# Sheet1.net
KiCad netlist of a schematic drawn in Altium Designer
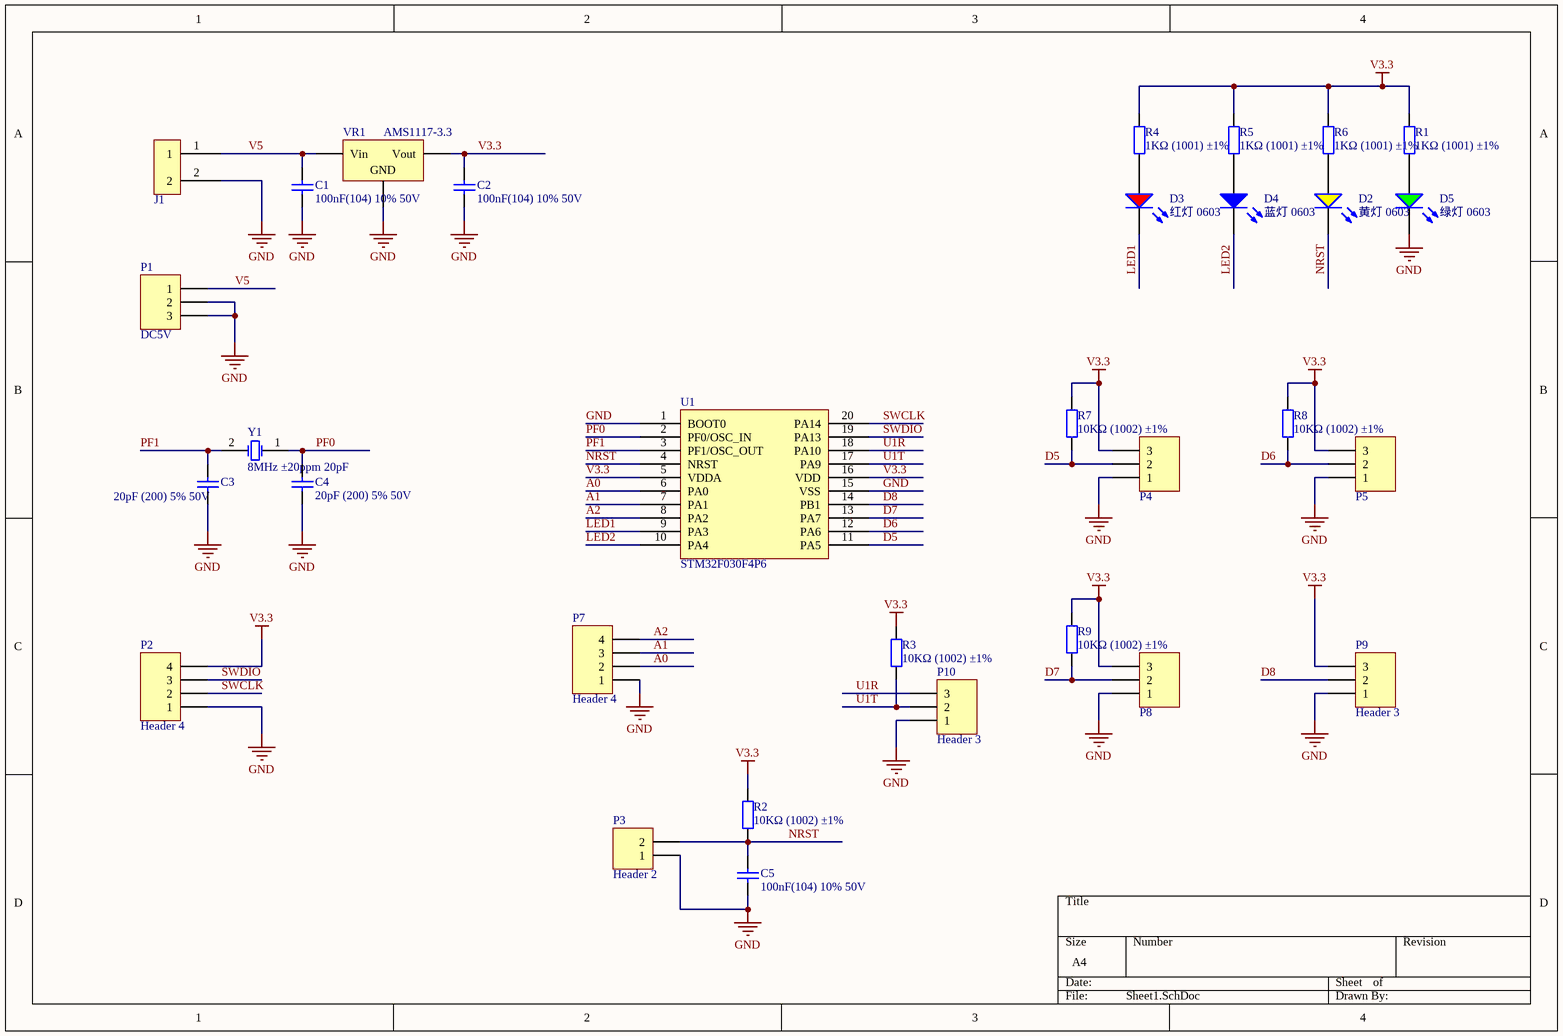
[diagram p0: Sheet1.SchDoc]

(export (version "E")
  (design (tool "Eeschema 10.0.6"))
  (components
    (comp (ref "C1")
      (value "100nF(104) 10% 50V")
      (footprint "0805_C")
      (description "贴片电容")
      (libsource (lib "Miscellaneous Devices LC") (part "0805 100nF(104) 10% 50V"))
    )
    (comp (ref "C2")
      (value "100nF(104) 10% 50V")
      (footprint "0805_C")
      (description "贴片电容")
      (libsource (lib "Miscellaneous Devices LC") (part "0805 100nF(104) 10% 50V"))
    )
    (comp (ref "C3")
      (value "20pF (200) 5% 50V")
      (footprint "0805_C")
      (description "贴片电容")
      (libsource (lib "Miscellaneous Devices LC") (part "0805 20pF (200) 5% 50V"))
    )
    (comp (ref "C4")
      (value "20pF (200) 5% 50V")
      (footprint "0805_C")
      (description "贴片电容")
      (libsource (lib "Miscellaneous Devices LC") (part "0805 20pF (200) 5% 50V"))
    )
    (comp (ref "C5")
      (value "100nF(104) 10% 50V")
      (footprint "0805_C")
      (description "贴片电容")
      (libsource (lib "Miscellaneous Devices LC") (part "0805 100nF(104) 10% 50V"))
    )
    (comp (ref "D2")
      (value "黄灯 0603")
      (footprint "0603_LED_S1")
      (description "发光二极管")
      (libsource (lib "Miscellaneous Devices LC") (part "0603 黄灯"))
    )
    (comp (ref "D3")
      (value "红灯 0603")
      (footprint "0603_LED_S1")
      (description "发光二极管")
      (libsource (lib "Miscellaneous Devices LC") (part "0603 红灯"))
    )
    (comp (ref "D4")
      (value "蓝灯 0603")
      (footprint "0603_LED_S1")
      (description "发光二极管")
      (libsource (lib "Miscellaneous Devices LC") (part "0603 蓝灯"))
    )
    (comp (ref "D5")
      (value "绿灯 0603")
      (footprint "0603_LED_S1")
      (description "发光二极管")
      (libsource (lib "Miscellaneous Devices LC") (part "0603 绿灯"))
    )
    (comp (ref "J1") (value "XK7.62-2P") (footprint "XK7.62-2P") (libsource (lib "CHK-I") (part "XK7.62-2P")))
    (comp (ref "P1")
      (value "DC5V")
      (footprint "DC005")
      (description "Header, 3-Pin")
      (fields (field (name "PUBLISHER") "Altium Limited"))
      (libsource (lib "") (part "Header 3_1"))
    )
    (comp (ref "P2")
      (value "Header 4")
      (footprint "HDR1X4")
      (description "Header, 4-Pin")
      (fields (field (name "PUBLISHER") "Altium Limited"))
      (libsource (lib "Miscellaneous Connectors") (part "Header 4"))
    )
    (comp (ref "P3")
      (value "Header 2")
      (footprint "HDR1X2")
      (description "Header, 2-Pin")
      (fields (field (name "PUBLISHER") "Altium Limited"))
      (libsource (lib "Miscellaneous Connectors") (part "Header 2"))
    )
    (comp (ref "P4")
      (value "Header 3")
      (footprint "HDR1X3")
      (description "Header, 3-Pin")
      (fields (field (name "PUBLISHER") "Altium Limited"))
      (libsource (lib "Miscellaneous Connectors") (part "Header 3"))
    )
    (comp (ref "P5")
      (value "Header 3")
      (footprint "HDR1X3")
      (description "Header, 3-Pin")
      (fields (field (name "PUBLISHER") "Altium Limited"))
      (libsource (lib "Miscellaneous Connectors") (part "Header 3"))
    )
    (comp (ref "P7")
      (value "Header 4")
      (footprint "HDR1X4")
      (description "Header, 4-Pin")
      (fields (field (name "PUBLISHER") "Altium Limited"))
      (libsource (lib "Miscellaneous Connectors") (part "Header 4"))
    )
    (comp (ref "P8")
      (value "Header 3")
      (footprint "HDR1X3")
      (description "Header, 3-Pin")
      (fields (field (name "PUBLISHER") "Altium Limited"))
      (libsource (lib "Miscellaneous Connectors") (part "Header 3"))
    )
    (comp (ref "P9")
      (value "Header 3")
      (footprint "HDR1X3")
      (description "Header, 3-Pin")
      (fields (field (name "PUBLISHER") "Altium Limited"))
      (libsource (lib "Miscellaneous Connectors") (part "Header 3"))
    )
    (comp (ref "P10")
      (value "Header 3")
      (footprint "HDR1X3")
      (description "Header, 3-Pin")
      (fields (field (name "PUBLISHER") "Altium Limited"))
      (libsource (lib "Miscellaneous Connectors") (part "Header 3"))
    )
    (comp (ref "R1")
      (value "1KΩ (1001) ±1%")
      (footprint "0805_R")
      (description "贴片电阻")
      (libsource (lib "Miscellaneous Devices LC") (part "0805 1KΩ (1001) 1%"))
    )
    (comp (ref "R2")
      (value "10KΩ (1002) ±1%")
      (footprint "0805_R")
      (description "贴片电阻")
      (libsource (lib "Miscellaneous Devices LC") (part "0805 10KΩ (1002) 1%"))
    )
    (comp (ref "R3")
      (value "10KΩ (1002) ±1%")
      (footprint "0805_R")
      (description "贴片电阻")
      (libsource (lib "Miscellaneous Devices LC") (part "0805 10KΩ (1002) 1%"))
    )
    (comp (ref "R4")
      (value "1KΩ (1001) ±1%")
      (footprint "0805_R")
      (description "贴片电阻")
      (libsource (lib "Miscellaneous Devices LC") (part "0805 1KΩ (1001) 1%"))
    )
    (comp (ref "R5")
      (value "1KΩ (1001) ±1%")
      (footprint "0805_R")
      (description "贴片电阻")
      (libsource (lib "Miscellaneous Devices LC") (part "0805 1KΩ (1001) 1%"))
    )
    (comp (ref "R6")
      (value "1KΩ (1001) ±1%")
      (footprint "0805_R")
      (description "贴片电阻")
      (libsource (lib "Miscellaneous Devices LC") (part "0805 1KΩ (1001) 1%"))
    )
    (comp (ref "R7")
      (value "10KΩ (1002) ±1%")
      (footprint "0805_R")
      (description "贴片电阻")
      (libsource (lib "Miscellaneous Devices LC") (part "0805 10KΩ (1002) 1%"))
    )
    (comp (ref "R8")
      (value "10KΩ (1002) ±1%")
      (footprint "0805_R")
      (description "贴片电阻")
      (libsource (lib "Miscellaneous Devices LC") (part "0805 10KΩ (1002) 1%"))
    )
    (comp (ref "R9")
      (value "10KΩ (1002) ±1%")
      (footprint "0805_R")
      (description "贴片电阻")
      (libsource (lib "Miscellaneous Devices LC") (part "0805 10KΩ (1002) 1%"))
    )
    (comp (ref "U1")
      (value "STM32F030F4P6")
      (footprint "TSSOP-20")
      (description "ARM")
      (libsource (lib "Miscellaneous Devices LC") (part "STM32F030F4P6"))
    )
    (comp (ref "VR1")
      (value "AMS1117-3.3")
      (footprint "SOT-223")
      (description "低压差线性稳压(LDO)")
      (libsource (lib "Miscellaneous Devices LC") (part "SOT-223 AMS1117-3.3"))
    )
    (comp (ref "Y1")
      (value "8MHz ±20ppm 20pF")
      (footprint "SMD-5032_2P")
      (description "贴片晶振")
      (libsource (lib "Miscellaneous Devices LC") (part "SMD-5032_2P 8MHz 20ppm 20pF"))
    )
  )
  (nets
    (net (code "1") (name "/A0") (class "Default")
      (node (ref "P7") (pin "2") (pinfunction "2_2") (pintype "passive"))
      (node (ref "U1") (pin "6") (pinfunction "PA0_6") (pintype "passive"))
    )
    (net (code "2") (name "/A1") (class "Default")
      (node (ref "P7") (pin "3") (pinfunction "3_3") (pintype "passive"))
      (node (ref "U1") (pin "7") (pinfunction "PA1_7") (pintype "passive"))
    )
    (net (code "3") (name "/A2") (class "Default")
      (node (ref "P7") (pin "4") (pinfunction "4_4") (pintype "passive"))
      (node (ref "U1") (pin "8") (pinfunction "PA2_8") (pintype "passive"))
    )
    (net (code "4") (name "/D5") (class "Default")
      (node (ref "P4") (pin "2") (pinfunction "2_2") (pintype "passive"))
      (node (ref "R7") (pin "1") (pinfunction "1_1") (pintype "passive"))
      (node (ref "U1") (pin "11") (pinfunction "PA5_11") (pintype "passive"))
    )
    (net (code "5") (name "/D6") (class "Default")
      (node (ref "P5") (pin "2") (pinfunction "2_2") (pintype "passive"))
      (node (ref "R8") (pin "1") (pinfunction "1_1") (pintype "passive"))
      (node (ref "U1") (pin "12") (pinfunction "PA6_12") (pintype "passive"))
    )
    (net (code "6") (name "/D7") (class "Default")
      (node (ref "P8") (pin "2") (pinfunction "2_2") (pintype "passive"))
      (node (ref "R9") (pin "1") (pinfunction "1_1") (pintype "passive"))
      (node (ref "U1") (pin "13") (pinfunction "PA7_13") (pintype "passive"))
    )
    (net (code "7") (name "/D8") (class "Default")
      (node (ref "P9") (pin "2") (pinfunction "2_2") (pintype "passive"))
      (node (ref "U1") (pin "14") (pinfunction "PB1_14") (pintype "passive"))
    )
    (net (code "8") (name "/LED1") (class "Default")
      (node (ref "D3") (pin "K") (pinfunction "K_K") (pintype "passive"))
      (node (ref "U1") (pin "9") (pinfunction "PA3_9") (pintype "passive"))
    )
    (net (code "9") (name "/LED2") (class "Default")
      (node (ref "D4") (pin "K") (pinfunction "K_K") (pintype "passive"))
      (node (ref "U1") (pin "10") (pinfunction "PA4_10") (pintype "passive"))
    )
    (net (code "10") (name "/NRST") (class "Default")
      (node (ref "C5") (pin "2") (pinfunction "2_2") (pintype "passive"))
      (node (ref "D2") (pin "K") (pinfunction "K_K") (pintype "passive"))
      (node (ref "P3") (pin "2") (pinfunction "2_2") (pintype "passive"))
      (node (ref "R2") (pin "1") (pinfunction "1_1") (pintype "passive"))
      (node (ref "U1") (pin "4") (pinfunction "NRST_4") (pintype "passive"))
    )
    (net (code "11") (name "/PF0") (class "Default")
      (node (ref "C4") (pin "2") (pinfunction "2_2") (pintype "passive"))
      (node (ref "U1") (pin "2") (pinfunction "PF0/OSC_IN_2") (pintype "passive"))
      (node (ref "Y1") (pin "1") (pinfunction "OSC1_1") (pintype "passive"))
    )
    (net (code "12") (name "/PF1") (class "Default")
      (node (ref "C3") (pin "2") (pinfunction "2_2") (pintype "passive"))
      (node (ref "U1") (pin "3") (pinfunction "PF1/OSC_OUT_3") (pintype "passive"))
      (node (ref "Y1") (pin "2") (pinfunction "OSC2_2") (pintype "passive"))
    )
    (net (code "13") (name "/SWCLK") (class "Default")
      (node (ref "P2") (pin "2") (pinfunction "2_2") (pintype "passive"))
      (node (ref "U1") (pin "20") (pinfunction "PA14_20") (pintype "passive"))
    )
    (net (code "14") (name "/SWDIO") (class "Default")
      (node (ref "P2") (pin "3") (pinfunction "3_3") (pintype "passive"))
      (node (ref "U1") (pin "19") (pinfunction "PA13_19") (pintype "passive"))
    )
    (net (code "15") (name "/U1R") (class "Default")
      (node (ref "P10") (pin "3") (pinfunction "3_3") (pintype "passive"))
      (node (ref "U1") (pin "18") (pinfunction "PA10_18") (pintype "passive"))
    )
    (net (code "16") (name "/U1T") (class "Default")
      (node (ref "P10") (pin "2") (pinfunction "2_2") (pintype "passive"))
      (node (ref "R3") (pin "1") (pinfunction "1_1") (pintype "passive"))
      (node (ref "U1") (pin "17") (pinfunction "PA9_17") (pintype "passive"))
    )
    (net (code "17") (name "/V5") (class "Default")
      (node (ref "C1") (pin "2") (pinfunction "2_2") (pintype "passive"))
      (node (ref "J1") (pin "1") (pinfunction "1_1") (pintype "passive"))
      (node (ref "P1") (pin "1") (pinfunction "1_1") (pintype "passive"))
      (node (ref "VR1") (pin "3") (pinfunction "Vin_3") (pintype "passive"))
    )
    (net (code "18") (name "GND") (class "Default")
      (node (ref "C1") (pin "1") (pinfunction "1_1") (pintype "passive"))
      (node (ref "C2") (pin "1") (pinfunction "1_1") (pintype "passive"))
      (node (ref "C3") (pin "1") (pinfunction "1_1") (pintype "passive"))
      (node (ref "C4") (pin "1") (pinfunction "1_1") (pintype "passive"))
      (node (ref "C5") (pin "1") (pinfunction "1_1") (pintype "passive"))
      (node (ref "D5") (pin "K") (pinfunction "K_K") (pintype "passive"))
      (node (ref "J1") (pin "2") (pinfunction "2_2") (pintype "passive"))
      (node (ref "P1") (pin "2") (pinfunction "2_2") (pintype "passive"))
      (node (ref "P1") (pin "3") (pinfunction "3_3") (pintype "passive"))
      (node (ref "P10") (pin "1") (pinfunction "1_1") (pintype "passive"))
      (node (ref "P2") (pin "1") (pinfunction "1_1") (pintype "passive"))
      (node (ref "P3") (pin "1") (pinfunction "1_1") (pintype "passive"))
      (node (ref "P4") (pin "1") (pinfunction "1_1") (pintype "passive"))
      (node (ref "P5") (pin "1") (pinfunction "1_1") (pintype "passive"))
      (node (ref "P7") (pin "1") (pinfunction "1_1") (pintype "passive"))
      (node (ref "P8") (pin "1") (pinfunction "1_1") (pintype "passive"))
      (node (ref "P9") (pin "1") (pinfunction "1_1") (pintype "passive"))
      (node (ref "U1") (pin "1") (pinfunction "BOOT0_1") (pintype "passive"))
      (node (ref "U1") (pin "15") (pinfunction "VSS_15") (pintype "passive"))
      (node (ref "VR1") (pin "1") (pinfunction "GND_1") (pintype "passive"))
    )
    (net (code "19") (name "Net-(D2-PadA)") (class "Default")
      (node (ref "D2") (pin "A") (pinfunction "A_A") (pintype "passive"))
      (node (ref "R6") (pin "1") (pinfunction "1_1") (pintype "passive"))
    )
    (net (code "20") (name "Net-(D3-PadA)") (class "Default")
      (node (ref "D3") (pin "A") (pinfunction "A_A") (pintype "passive"))
      (node (ref "R4") (pin "1") (pinfunction "1_1") (pintype "passive"))
    )
    (net (code "21") (name "Net-(D4-PadA)") (class "Default")
      (node (ref "D4") (pin "A") (pinfunction "A_A") (pintype "passive"))
      (node (ref "R5") (pin "1") (pinfunction "1_1") (pintype "passive"))
    )
    (net (code "22") (name "Net-(D5-PadA)") (class "Default")
      (node (ref "D5") (pin "A") (pinfunction "A_A") (pintype "passive"))
      (node (ref "R1") (pin "1") (pinfunction "1_1") (pintype "passive"))
    )
    (net (code "23") (name "V3.3") (class "Default")
      (node (ref "C2") (pin "2") (pinfunction "2_2") (pintype "passive"))
      (node (ref "P2") (pin "4") (pinfunction "4_4") (pintype "passive"))
      (node (ref "P4") (pin "3") (pinfunction "3_3") (pintype "passive"))
      (node (ref "P5") (pin "3") (pinfunction "3_3") (pintype "passive"))
      (node (ref "P8") (pin "3") (pinfunction "3_3") (pintype "passive"))
      (node (ref "P9") (pin "3") (pinfunction "3_3") (pintype "passive"))
      (node (ref "R1") (pin "2") (pinfunction "2_2") (pintype "passive"))
      (node (ref "R2") (pin "2") (pinfunction "2_2") (pintype "passive"))
      (node (ref "R3") (pin "2") (pinfunction "2_2") (pintype "passive"))
      (node (ref "R4") (pin "2") (pinfunction "2_2") (pintype "passive"))
      (node (ref "R5") (pin "2") (pinfunction "2_2") (pintype "passive"))
      (node (ref "R6") (pin "2") (pinfunction "2_2") (pintype "passive"))
      (node (ref "R7") (pin "2") (pinfunction "2_2") (pintype "passive"))
      (node (ref "R8") (pin "2") (pinfunction "2_2") (pintype "passive"))
      (node (ref "R9") (pin "2") (pinfunction "2_2") (pintype "passive"))
      (node (ref "U1") (pin "16") (pinfunction "VDD_16") (pintype "passive"))
      (node (ref "U1") (pin "5") (pinfunction "VDDA_5") (pintype "passive"))
      (node (ref "VR1") (pin "2") (pinfunction "Vout_2") (pintype "passive"))
    )
  )
)
